# Equilibrium-PCB.net
KiCad netlist of a schematic drawn in EasyEDA
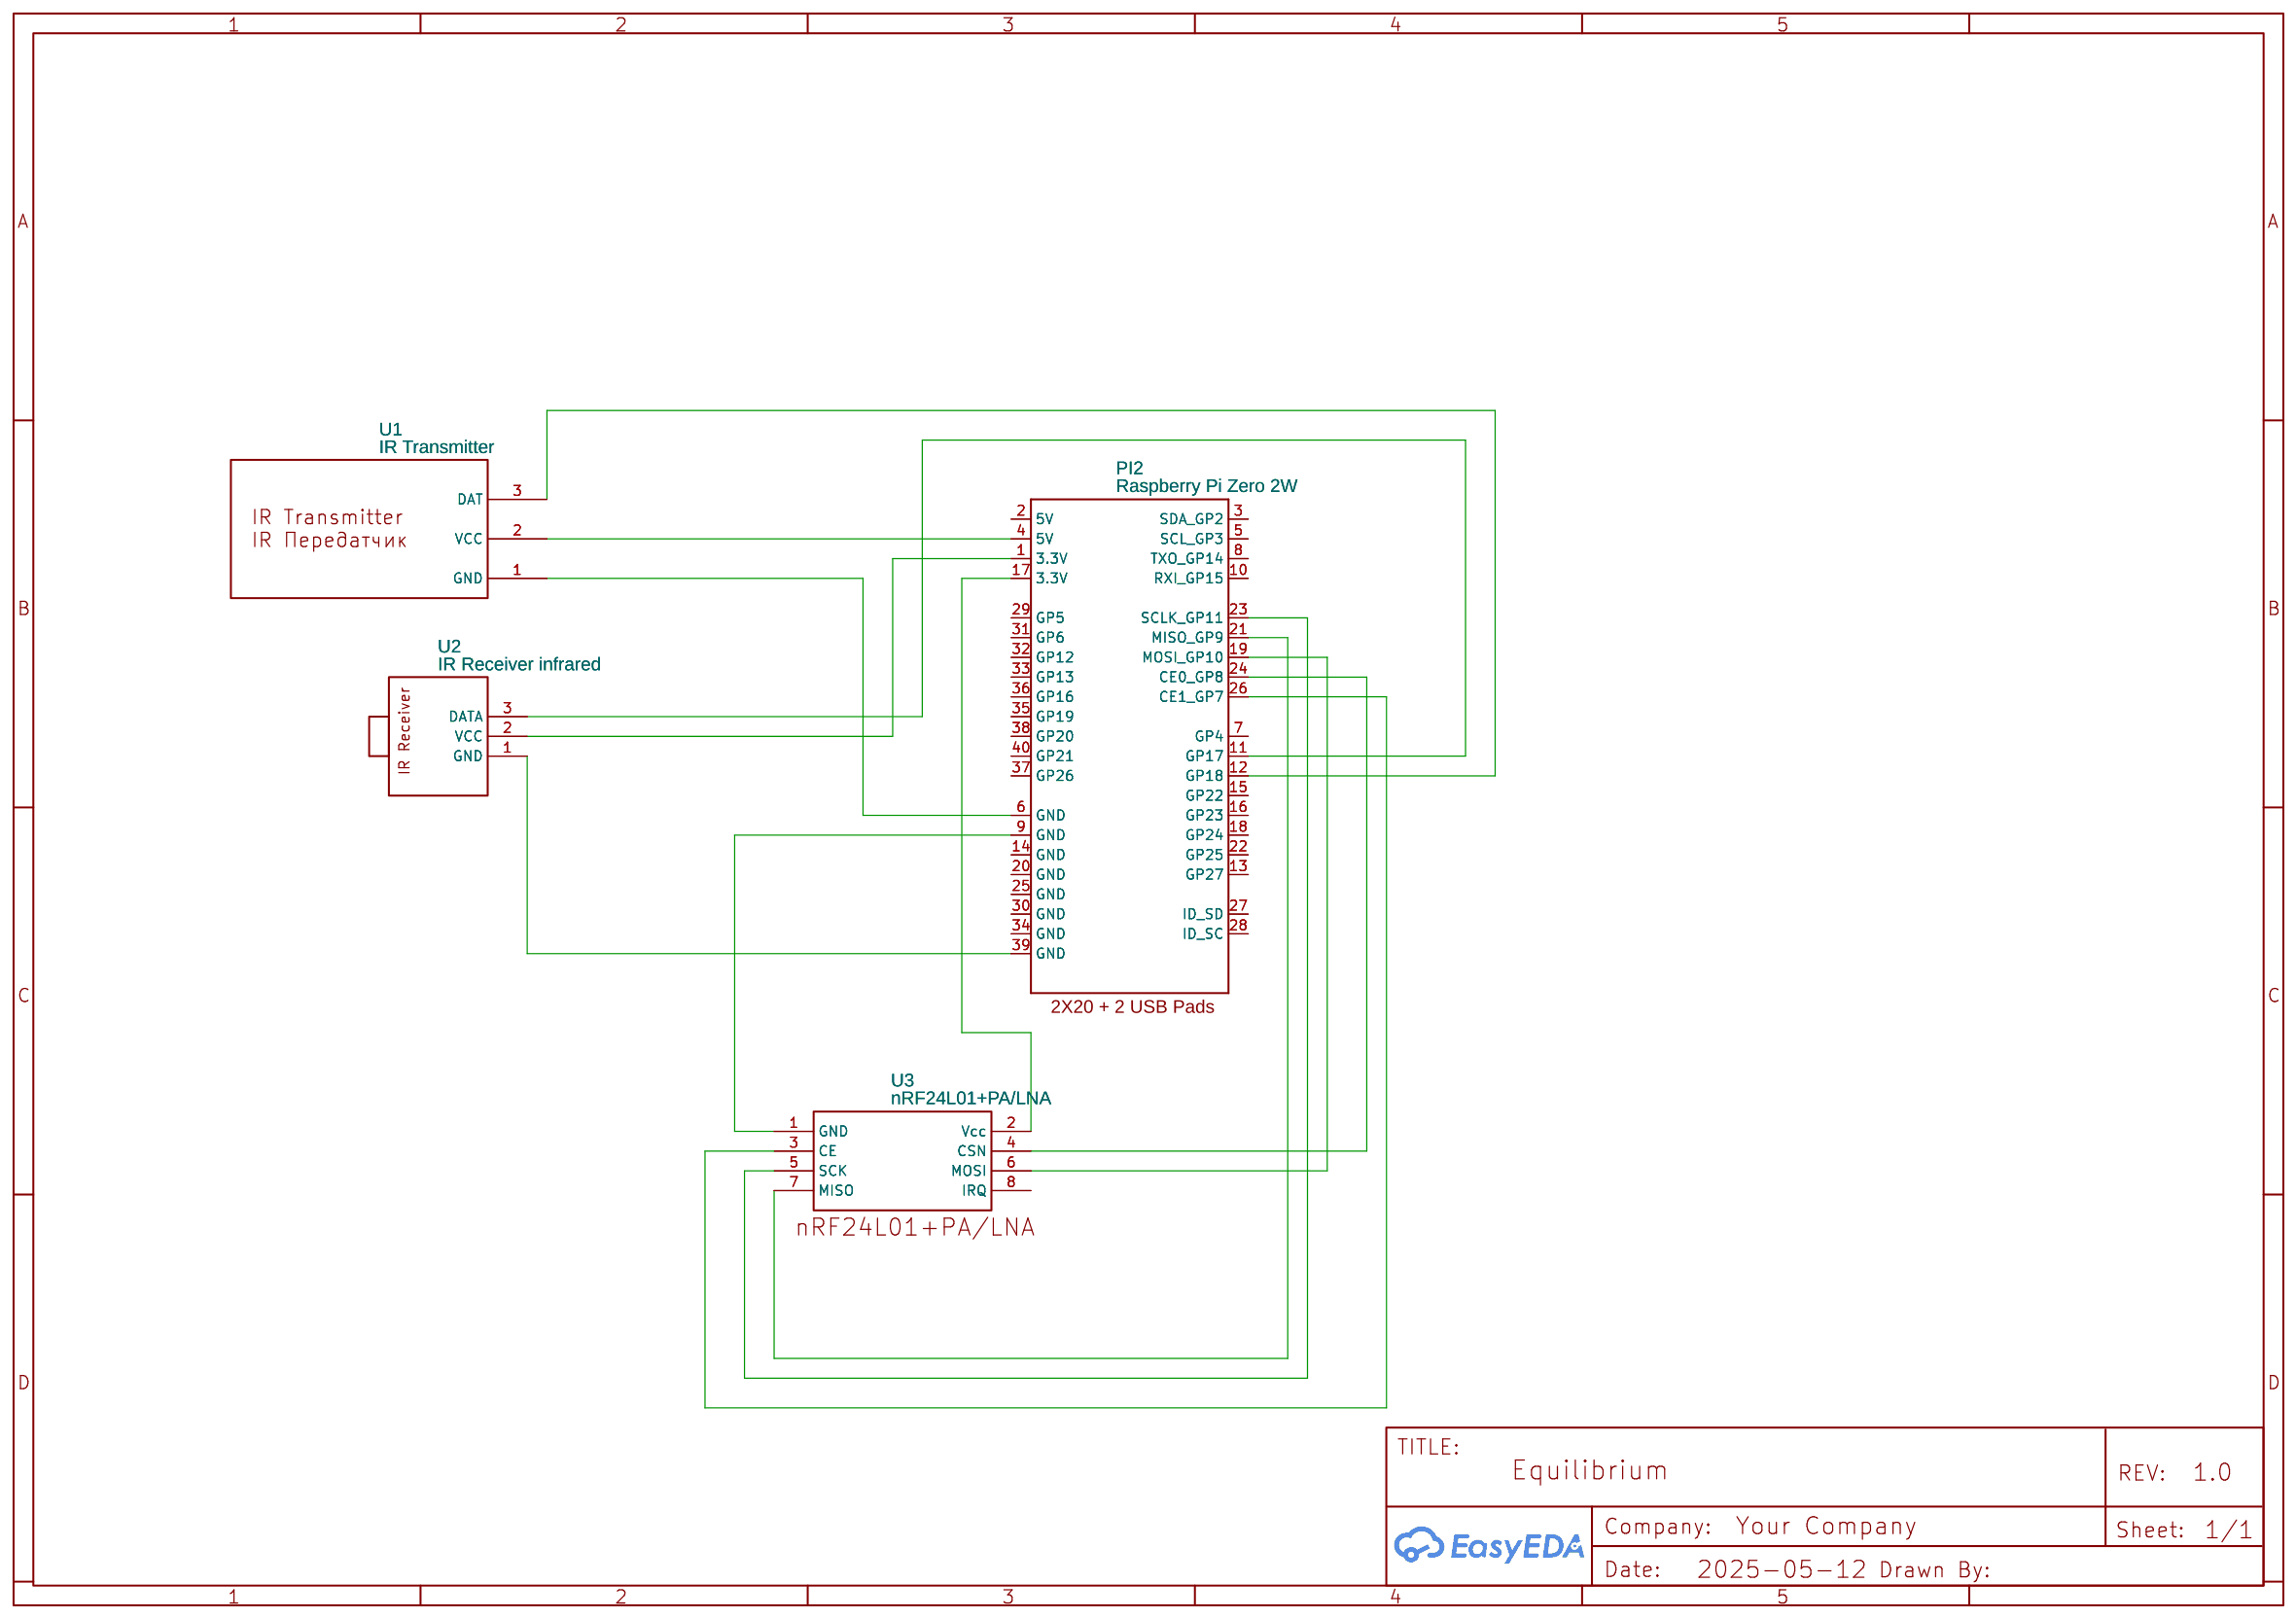
[diagram p0: schematic sheet]

(export (version "E")
  (design (tool "Eeschema 10.0.6"))
  (components
    (comp (ref "PI2")
      (value "Raspberry Pi Zero 2W")
      (fields (field (name "Manufacturer") "Raspberry Pi"))
      (libsource (lib "") (part "Raspberry Pi Zero 2W lka"))
    )
    (comp (ref "U1") (value "IR Transmitter") (libsource (lib "") (part "IR Transmitter")))
    (comp (ref "U2") (value "IR Receiver infrared") (libsource (lib "") (part "IR Receiver infrared")))
    (comp (ref "U3") (value "nRF24L01+PA/LNA") (libsource (lib "") (part "nRF24L01+PA/LNA")))
  )
  (nets
    (net (code "1") (name "Net-(PI2-CE0_GP8)") (class "Default")
      (node (ref "PI2") (pin "24") (pinfunction "CE0_GP8_24") (pintype "bidirectional"))
      (node (ref "U3") (pin "4") (pinfunction "CSN_4") (pintype "unspecified"))
    )
    (net (code "2") (name "Net-(PI2-CE1_GP7)") (class "Default")
      (node (ref "PI2") (pin "26") (pinfunction "CE1_GP7_26") (pintype "bidirectional"))
      (node (ref "U3") (pin "3") (pinfunction "CE_3") (pintype "unspecified"))
    )
    (net (code "3") (name "Net-(PI2-GP17)") (class "Default")
      (node (ref "PI2") (pin "11") (pinfunction "GP17_11") (pintype "bidirectional"))
      (node (ref "U2") (pin "3") (pinfunction "DATA_3") (pintype "unspecified"))
    )
    (net (code "4") (name "Net-(PI2-GP18)") (class "Default")
      (node (ref "PI2") (pin "12") (pinfunction "GP18_12") (pintype "bidirectional"))
      (node (ref "U1") (pin "3") (pinfunction "DAT_3") (pintype "unspecified"))
    )
    (net (code "5") (name "Net-(PI2-MISO_GP9)") (class "Default")
      (node (ref "PI2") (pin "21") (pinfunction "MISO_GP9_21") (pintype "bidirectional"))
      (node (ref "U3") (pin "7") (pinfunction "MISO_7") (pintype "unspecified"))
    )
    (net (code "6") (name "Net-(PI2-MOSI_GP10)") (class "Default")
      (node (ref "PI2") (pin "19") (pinfunction "MOSI_GP10_19") (pintype "bidirectional"))
      (node (ref "U3") (pin "6") (pinfunction "MOSI_6") (pintype "unspecified"))
    )
    (net (code "7") (name "Net-(PI2-SCLK_GP11)") (class "Default")
      (node (ref "PI2") (pin "23") (pinfunction "SCLK_GP11_23") (pintype "bidirectional"))
      (node (ref "U3") (pin "5") (pinfunction "SCK_5") (pintype "unspecified"))
    )
    (net (code "8") (name "Net-(U1-GND)") (class "Default")
      (node (ref "PI2") (pin "6") (pinfunction "GND_6") (pintype "passive"))
      (node (ref "U1") (pin "1") (pinfunction "GND_1") (pintype "unspecified"))
    )
    (net (code "9") (name "Net-(U1-VCC)") (class "Default")
      (node (ref "PI2") (pin "4") (pinfunction "5V_4") (pintype "passive"))
      (node (ref "U1") (pin "2") (pinfunction "VCC_2") (pintype "unspecified"))
    )
    (net (code "10") (name "Net-(U2-GND)") (class "Default")
      (node (ref "PI2") (pin "39") (pinfunction "GND_39") (pintype "passive"))
      (node (ref "U2") (pin "1") (pinfunction "GND_1") (pintype "unspecified"))
    )
    (net (code "11") (name "Net-(U2-VCC)") (class "Default")
      (node (ref "PI2") (pin "1") (pinfunction "3.3V_1") (pintype "passive"))
      (node (ref "U2") (pin "2") (pinfunction "VCC_2") (pintype "unspecified"))
    )
    (net (code "12") (name "Net-(U3-GND)") (class "Default")
      (node (ref "PI2") (pin "9") (pinfunction "GND_9") (pintype "passive"))
      (node (ref "U3") (pin "1") (pinfunction "GND_1") (pintype "unspecified"))
    )
    (net (code "13") (name "Net-(U3-Vcc)") (class "Default")
      (node (ref "PI2") (pin "17") (pinfunction "3.3V_17") (pintype "passive"))
      (node (ref "U3") (pin "2") (pinfunction "Vcc_2") (pintype "unspecified"))
    )
    (net (code "14") (name "unconnected-(PI2-5V-Pad2)") (class "Default")
      (node (ref "PI2") (pin "2") (pinfunction "5V_2") (pintype "passive"))
    )
    (net (code "15") (name "unconnected-(PI2-GND-Pad14)") (class "Default")
      (node (ref "PI2") (pin "14") (pinfunction "GND_14") (pintype "passive"))
    )
    (net (code "16") (name "unconnected-(PI2-GND-Pad20)") (class "Default")
      (node (ref "PI2") (pin "20") (pinfunction "GND_20") (pintype "passive"))
    )
    (net (code "17") (name "unconnected-(PI2-GND-Pad25)") (class "Default")
      (node (ref "PI2") (pin "25") (pinfunction "GND_25") (pintype "passive"))
    )
    (net (code "18") (name "unconnected-(PI2-GND-Pad30)") (class "Default")
      (node (ref "PI2") (pin "30") (pinfunction "GND_30") (pintype "passive"))
    )
    (net (code "19") (name "unconnected-(PI2-GND-Pad34)") (class "Default")
      (node (ref "PI2") (pin "34") (pinfunction "GND_34") (pintype "passive"))
    )
    (net (code "20") (name "unconnected-(PI2-GP4-Pad7)") (class "Default")
      (node (ref "PI2") (pin "7") (pinfunction "GP4_7") (pintype "bidirectional"))
    )
    (net (code "21") (name "unconnected-(PI2-GP5-Pad29)") (class "Default")
      (node (ref "PI2") (pin "29") (pinfunction "GP5_29") (pintype "bidirectional"))
    )
    (net (code "22") (name "unconnected-(PI2-GP6-Pad31)") (class "Default")
      (node (ref "PI2") (pin "31") (pinfunction "GP6_31") (pintype "bidirectional"))
    )
    (net (code "23") (name "unconnected-(PI2-GP12-Pad32)") (class "Default")
      (node (ref "PI2") (pin "32") (pinfunction "GP12_32") (pintype "bidirectional"))
    )
    (net (code "24") (name "unconnected-(PI2-GP13-Pad33)") (class "Default")
      (node (ref "PI2") (pin "33") (pinfunction "GP13_33") (pintype "bidirectional"))
    )
    (net (code "25") (name "unconnected-(PI2-GP16-Pad36)") (class "Default")
      (node (ref "PI2") (pin "36") (pinfunction "GP16_36") (pintype "bidirectional"))
    )
    (net (code "26") (name "unconnected-(PI2-GP19-Pad35)") (class "Default")
      (node (ref "PI2") (pin "35") (pinfunction "GP19_35") (pintype "bidirectional"))
    )
    (net (code "27") (name "unconnected-(PI2-GP20-Pad38)") (class "Default")
      (node (ref "PI2") (pin "38") (pinfunction "GP20_38") (pintype "bidirectional"))
    )
    (net (code "28") (name "unconnected-(PI2-GP21-Pad40)") (class "Default")
      (node (ref "PI2") (pin "40") (pinfunction "GP21_40") (pintype "bidirectional"))
    )
    (net (code "29") (name "unconnected-(PI2-GP22-Pad15)") (class "Default")
      (node (ref "PI2") (pin "15") (pinfunction "GP22_15") (pintype "bidirectional"))
    )
    (net (code "30") (name "unconnected-(PI2-GP23-Pad16)") (class "Default")
      (node (ref "PI2") (pin "16") (pinfunction "GP23_16") (pintype "bidirectional"))
    )
    (net (code "31") (name "unconnected-(PI2-GP24-Pad18)") (class "Default")
      (node (ref "PI2") (pin "18") (pinfunction "GP24_18") (pintype "bidirectional"))
    )
    (net (code "32") (name "unconnected-(PI2-GP25-Pad22)") (class "Default")
      (node (ref "PI2") (pin "22") (pinfunction "GP25_22") (pintype "bidirectional"))
    )
    (net (code "33") (name "unconnected-(PI2-GP26-Pad37)") (class "Default")
      (node (ref "PI2") (pin "37") (pinfunction "GP26_37") (pintype "bidirectional"))
    )
    (net (code "34") (name "unconnected-(PI2-GP27-Pad13)") (class "Default")
      (node (ref "PI2") (pin "13") (pinfunction "GP27_13") (pintype "bidirectional"))
    )
    (net (code "35") (name "unconnected-(PI2-ID_SC-Pad28)") (class "Default")
      (node (ref "PI2") (pin "28") (pinfunction "ID_SC_28") (pintype "unspecified"))
    )
    (net (code "36") (name "unconnected-(PI2-ID_SD-Pad27)") (class "Default")
      (node (ref "PI2") (pin "27") (pinfunction "ID_SD_27") (pintype "unspecified"))
    )
    (net (code "37") (name "unconnected-(PI2-RXI_GP15-Pad10)") (class "Default")
      (node (ref "PI2") (pin "10") (pinfunction "RXI_GP15_10") (pintype "bidirectional"))
    )
    (net (code "38") (name "unconnected-(PI2-SCL_GP3-Pad5)") (class "Default")
      (node (ref "PI2") (pin "5") (pinfunction "SCL_GP3_5") (pintype "bidirectional"))
    )
    (net (code "39") (name "unconnected-(PI2-SDA_GP2-Pad3)") (class "Default")
      (node (ref "PI2") (pin "3") (pinfunction "SDA_GP2_3") (pintype "bidirectional"))
    )
    (net (code "40") (name "unconnected-(PI2-TXO_GP14-Pad8)") (class "Default")
      (node (ref "PI2") (pin "8") (pinfunction "TXO_GP14_8") (pintype "bidirectional"))
    )
    (net (code "41") (name "unconnected-(U3-IRQ-Pad8)") (class "Default")
      (node (ref "U3") (pin "8") (pinfunction "IRQ_8") (pintype "unspecified"))
    )
  )
)
